# B293A_CoX_Amp.net
KiCad netlist of a schematic drawn in Altium Designer
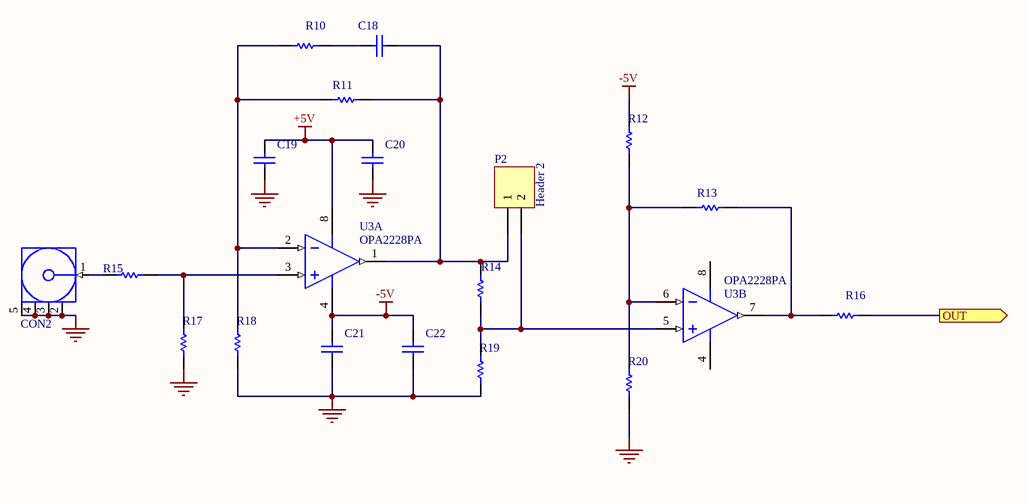
[diagram p0: B293A CoX Amp.SchDoc]

(export (version "E")
  (design (tool "Eeschema 10.0.6"))
  (components
    (comp (ref "C18")
      (value "CAP 47pF 50V 0805(2012)")
      (footprint "CAPC0805(2012)75_L")
      (description "CAP 47pF 50V ±5% 0805 (2012 Metric) Thickness 0.75mm SMD")
      (fields (field (name "TOLERANCE") "±5%"))
      (libsource (lib "Altium Content Vault") (part "CAP"))
    )
    (comp (ref "C19")
      (value "CAP 10uF 25V 0805(2012)")
      (footprint "CAPC0805(2012)145_N")
      (description "CAP 10uF 25V ±20% 0805 (2012 Metric) Thickness 1.45mm SMD")
      (fields (field (name "TOLERANCE") "±20%"))
      (libsource (lib "Altium Content Vault") (part "CAP"))
    )
    (comp (ref "C20")
      (value "CAP 10nF 25V 0805(2012)")
      (footprint "CAPC0805(2012)75_L")
      (description "CAP 10nF 25V ±10% 0805 (2012 Metric) Thickness 0.75mm SMD")
      (fields (field (name "TOLERANCE") "±10%"))
      (libsource (lib "Altium Content Vault") (part "CAP"))
    )
    (comp (ref "C21")
      (value "CAP 10nF 25V 0805(2012)")
      (footprint "CAPC0805(2012)75_L")
      (description "CAP 10nF 25V ±10% 0805 (2012 Metric) Thickness 0.75mm SMD")
      (fields (field (name "TOLERANCE") "±10%"))
      (libsource (lib "Altium Content Vault") (part "CAP"))
    )
    (comp (ref "C22")
      (value "CAP 10uF 25V 0805(2012)")
      (footprint "CAPC0805(2012)145_N")
      (description "CAP 10uF 25V ±20% 0805 (2012 Metric) Thickness 1.45mm SMD")
      (fields (field (name "TOLERANCE") "±20%"))
      (libsource (lib "Altium Content Vault") (part "CAP"))
    )
    (comp (ref "CON2")
      (value "SMA Vertical")
      (footprint "Matt PCB Library:SMA Vertical")
      (fields (field (name "MANUFACTURERS PART NO") "5-1814832-1"))
      (libsource (lib "Matt SCH Library") (part "SMA Vertical"))
    )
    (comp (ref "P2")
      (value "Header 2")
      (footprint "HDR1X2")
      (description "Header, 2-Pin")
      (fields (field (name "PUBLISHER") "Altium Limited"))
      (libsource (lib "Miscellaneous Connectors") (part "Header 2"))
    )
    (comp (ref "R10")
      (value "1K5 5% 0805(2012)")
      (footprint "RESC0805(2012)_L")
      (description "1K5 0.125W 5% 0805 (2012 Metric)  SMD")
      (fields (field (name "TOLERANCE") "5 %") (field (name "POWER") "0.125 W"))
      (libsource (lib "Altium Content Vault") (part "RES"))
    )
    (comp (ref "R11")
      (value "100K 5% 0805(2012)")
      (footprint "RESC0805(2012)_L")
      (description "100K 0.125W 5% 0805 (2012 Metric)  SMD")
      (fields (field (name "TOLERANCE") "5 %") (field (name "POWER") "0.125 W"))
      (libsource (lib "Altium Content Vault") (part "RES"))
    )
    (comp (ref "R12")
      (value "150K 5% 0805(2012)")
      (footprint "RESC0805(2012)_N")
      (description "150K 0.125W 5% 0805 (2012 Metric)  SMD")
      (fields (field (name "TOLERANCE") "5 %") (field (name "POWER") "0.125 W"))
      (libsource (lib "Altium Content Vault") (part "RES"))
    )
    (comp (ref "R13")
      (value "10K 5% 0805(2012)")
      (footprint "RESC0805(2012)_L")
      (description "10K 0.125W 5% 0805 (2012 Metric)  SMD")
      (fields (field (name "TOLERANCE") "5 %") (field (name "POWER") "0.125 W"))
      (libsource (lib "Altium Content Vault") (part "RES"))
    )
    (comp (ref "R14")
      (value "10K 5% 0805(2012)")
      (footprint "RESC0805(2012)_L")
      (description "10K 0.125W 5% 0805 (2012 Metric)  SMD")
      (fields (field (name "TOLERANCE") "5 %") (field (name "POWER") "0.125 W"))
      (libsource (lib "Altium Content Vault") (part "RES"))
    )
    (comp (ref "R15")
      (value "100R 5% 0805(2012)")
      (footprint "RESC0805(2012)_M")
      (description "100R 0.125W 5% 0805 (2012 Metric)  SMD")
      (fields (field (name "TOLERANCE") "5 %") (field (name "POWER") "0.125 W"))
      (libsource (lib "Altium Content Vault") (part "RES"))
    )
    (comp (ref "R16")
      (value "100R 5% 0805(2012)")
      (footprint "RESC0805(2012)_M")
      (description "100R 0.125W 5% 0805 (2012 Metric)  SMD")
      (fields (field (name "TOLERANCE") "5 %") (field (name "POWER") "0.125 W"))
      (libsource (lib "Altium Content Vault") (part "RES"))
    )
    (comp (ref "R17")
      (value "27K 5% 0805(2012)")
      (footprint "RESC0805(2012)_L")
      (description "27K 0.125W 5% 0805 (2012 Metric)  SMD")
      (fields (field (name "TOLERANCE") "5 %") (field (name "POWER") "0.125 W"))
      (libsource (lib "Altium Content Vault") (part "RES"))
    )
    (comp (ref "R18")
      (value "330R 5% 0805(2012)")
      (footprint "RESC0805(2012)_L")
      (description "330R 0.125W 5% 0805 (2012 Metric)  SMD")
      (fields (field (name "TOLERANCE") "5 %") (field (name "POWER") "0.125 W"))
      (libsource (lib "Altium Content Vault") (part "RES"))
    )
    (comp (ref "R19")
      (value "1K2 5% 0805(2012)")
      (footprint "RESC0805(2012)_N")
      (description "1K2 0.125W 5% 0805 (2012 Metric)  SMD")
      (fields (field (name "TOLERANCE") "5 %") (field (name "POWER") "0.125 W"))
      (libsource (lib "Altium Content Vault") (part "RES"))
    )
    (comp (ref "R20")
      (value "1K2 5% 0805(2012)")
      (footprint "RESC0805(2012)_N")
      (description "1K2 0.125W 5% 0805 (2012 Metric)  SMD")
      (fields (field (name "TOLERANCE") "5 %") (field (name "POWER") "0.125 W"))
      (libsource (lib "Altium Content Vault") (part "RES"))
    )
    (comp (ref "U3")
      (value "OPA2228PA")
      (footprint "TI-P8")
      (fields (field (name "MANUFACTURER") "Texas Instruments"))
      (libsource (lib "Altium Content Vault") (part "TI-OPA-8_2"))
    )
  )
  (nets
    (net (code "1") (name "+5V") (class "Default")
      (node (ref "C19") (pin "2") (pinfunction "2_2") (pintype "passive"))
      (node (ref "C20") (pin "2") (pinfunction "2_2") (pintype "passive"))
      (node (ref "U3") (pin "8") (pinfunction "V+_8") (pintype "power_in"))
    )
    (net (code "2") (name "-5V") (class "Default")
      (node (ref "C21") (pin "2") (pinfunction "2_2") (pintype "passive"))
      (node (ref "C22") (pin "2") (pinfunction "2_2") (pintype "passive"))
      (node (ref "R12") (pin "2") (pinfunction "2_2") (pintype "passive"))
      (node (ref "U3") (pin "4") (pinfunction "V-_4") (pintype "power_in"))
    )
    (net (code "3") (name "/OUT") (class "Default")
      (node (ref "R16") (pin "2") (pinfunction "2_2") (pintype "passive"))
    )
    (net (code "4") (name "GND") (class "Default")
      (node (ref "C19") (pin "1") (pinfunction "1_1") (pintype "passive"))
      (node (ref "C20") (pin "1") (pinfunction "1_1") (pintype "passive"))
      (node (ref "C21") (pin "1") (pinfunction "1_1") (pintype "passive"))
      (node (ref "C22") (pin "1") (pinfunction "1_1") (pintype "passive"))
      (node (ref "CON2") (pin "2") (pinfunction "GND_2") (pintype "power_in"))
      (node (ref "CON2") (pin "3") (pinfunction "GND_3") (pintype "power_in"))
      (node (ref "CON2") (pin "4") (pinfunction "GND_4") (pintype "power_in"))
      (node (ref "CON2") (pin "5") (pinfunction "GND_5") (pintype "power_in"))
      (node (ref "R17") (pin "1") (pinfunction "1_1") (pintype "passive"))
      (node (ref "R18") (pin "1") (pinfunction "1_1") (pintype "passive"))
      (node (ref "R19") (pin "1") (pinfunction "1_1") (pintype "passive"))
      (node (ref "R20") (pin "1") (pinfunction "1_1") (pintype "passive"))
    )
    (net (code "5") (name "Net-(C18-Pad2)") (class "Default")
      (node (ref "C18") (pin "2") (pinfunction "2_2") (pintype "passive"))
      (node (ref "R10") (pin "2") (pinfunction "2_2") (pintype "passive"))
    )
    (net (code "6") (name "Net-(CON2-Signal)") (class "Default")
      (node (ref "CON2") (pin "1") (pinfunction "Signal_1") (pintype "input"))
      (node (ref "R15") (pin "2") (pinfunction "2_2") (pintype "passive"))
    )
    (net (code "7") (name "Net-(U3A-IN_A+)") (class "Default")
      (node (ref "R15") (pin "1") (pinfunction "1_1") (pintype "passive"))
      (node (ref "R17") (pin "2") (pinfunction "2_2") (pintype "passive"))
      (node (ref "U3") (pin "3") (pinfunction "IN_A+_3") (pintype "input"))
    )
    (net (code "8") (name "Net-(U3A-IN_A-)") (class "Default")
      (node (ref "R10") (pin "1") (pinfunction "1_1") (pintype "passive"))
      (node (ref "R11") (pin "1") (pinfunction "1_1") (pintype "passive"))
      (node (ref "R18") (pin "2") (pinfunction "2_2") (pintype "passive"))
      (node (ref "U3") (pin "2") (pinfunction "IN_A-_2") (pintype "input"))
    )
    (net (code "9") (name "Net-(U3A-OUT_A)") (class "Default")
      (node (ref "C18") (pin "1") (pinfunction "1_1") (pintype "passive"))
      (node (ref "P2") (pin "1") (pinfunction "1_1") (pintype "passive"))
      (node (ref "R11") (pin "2") (pinfunction "2_2") (pintype "passive"))
      (node (ref "R14") (pin "2") (pinfunction "2_2") (pintype "passive"))
      (node (ref "U3") (pin "1") (pinfunction "OUT_A_1") (pintype "output"))
    )
    (net (code "10") (name "Net-(U3B-IN_B+)") (class "Default")
      (node (ref "P2") (pin "2") (pinfunction "2_2") (pintype "passive"))
      (node (ref "R14") (pin "1") (pinfunction "1_1") (pintype "passive"))
      (node (ref "R19") (pin "2") (pinfunction "2_2") (pintype "passive"))
      (node (ref "U3") (pin "5") (pinfunction "IN_B+_5") (pintype "input"))
    )
    (net (code "11") (name "Net-(U3B-IN_B-)") (class "Default")
      (node (ref "R12") (pin "1") (pinfunction "1_1") (pintype "passive"))
      (node (ref "R13") (pin "1") (pinfunction "1_1") (pintype "passive"))
      (node (ref "R20") (pin "2") (pinfunction "2_2") (pintype "passive"))
      (node (ref "U3") (pin "6") (pinfunction "IN_B-_6") (pintype "input"))
    )
    (net (code "12") (name "Net-(U3B-OUT_B)") (class "Default")
      (node (ref "R13") (pin "2") (pinfunction "2_2") (pintype "passive"))
      (node (ref "R16") (pin "1") (pinfunction "1_1") (pintype "passive"))
      (node (ref "U3") (pin "7") (pinfunction "OUT_B_7") (pintype "output"))
    )
    (net (code "13") (name "unconnected-(U3B-V+-Pad8)") (class "Default")
      (node (ref "U3") (pin "8") (pinfunction "V+_8") (pintype "power_in"))
    )
    (net (code "14") (name "unconnected-(U3B-V--Pad4)") (class "Default")
      (node (ref "U3") (pin "4") (pinfunction "V-_4") (pintype "power_in"))
    )
  )
)
